# uc4h_airspeed_v0401.net
KiCad netlist of a schematic drawn in EAGLE
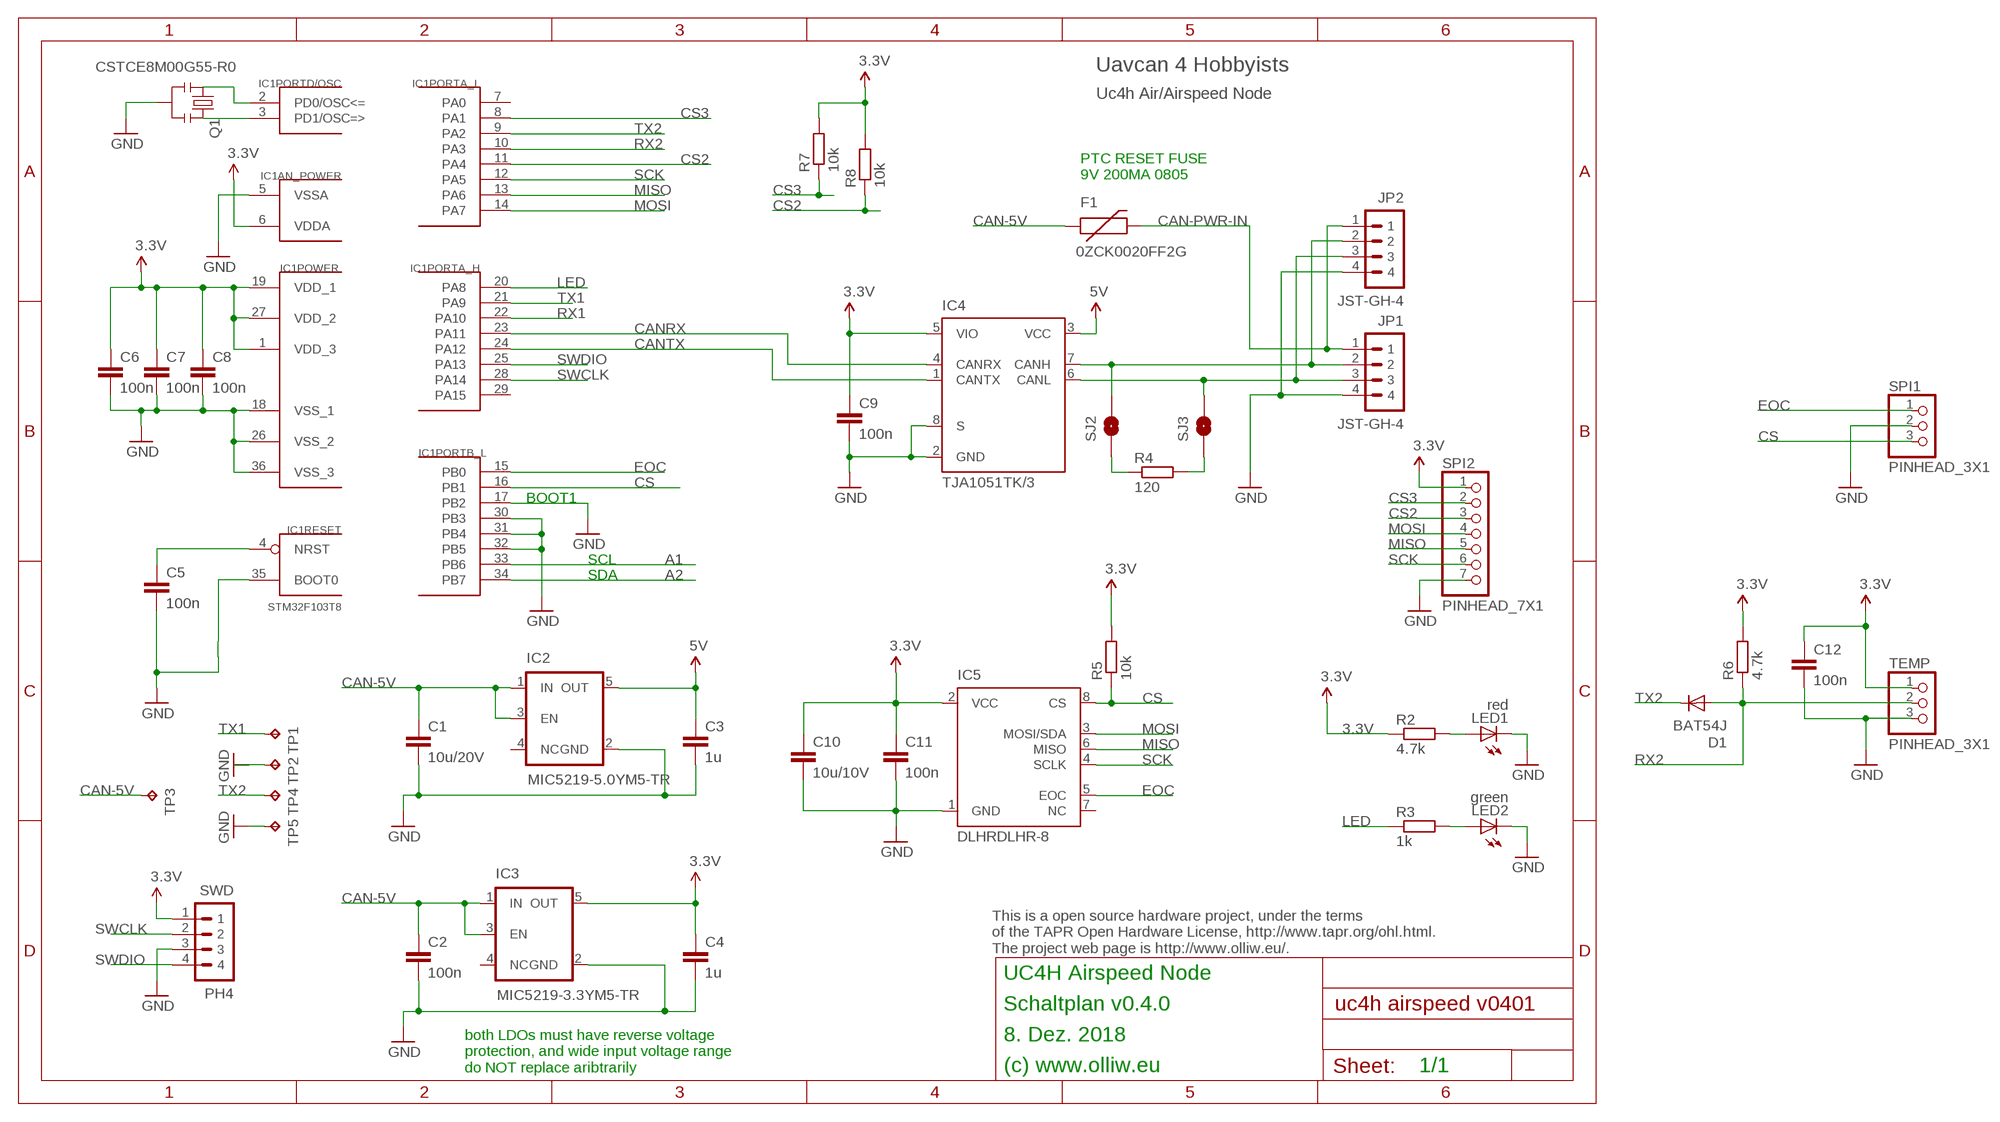
[diagram p0: schematic, sheet 1]

(export (version "E")
  (design (tool "Eeschema 10.0.6"))
  (components
    (comp (ref "C1")
      (value "10u/20V")
      (footprint "eagle-import:C1206")
      (libsource (lib "eagle-import") (part "C-EUC1206"))
    )
    (comp (ref "C2")
      (value "100n")
      (footprint "eagle-import:C0603K")
      (libsource (lib "eagle-import") (part "C-EUC0603K"))
    )
    (comp (ref "C3")
      (value "1u")
      (footprint "eagle-import:C0603K")
      (libsource (lib "eagle-import") (part "C-EUC0603K"))
    )
    (comp (ref "C4")
      (value "1u")
      (footprint "eagle-import:C0603K")
      (libsource (lib "eagle-import") (part "C-EUC0603K"))
    )
    (comp (ref "C5")
      (value "100n")
      (footprint "eagle-import:C0603K")
      (libsource (lib "eagle-import") (part "C-EUC0603K"))
    )
    (comp (ref "C6")
      (value "100n")
      (footprint "eagle-import:C0603K")
      (libsource (lib "eagle-import") (part "C-EUC0603K"))
    )
    (comp (ref "C7")
      (value "100n")
      (footprint "eagle-import:C0603K")
      (libsource (lib "eagle-import") (part "C-EUC0603K"))
    )
    (comp (ref "C8")
      (value "100n")
      (footprint "eagle-import:C0603K")
      (libsource (lib "eagle-import") (part "C-EUC0603K"))
    )
    (comp (ref "C9")
      (value "100n")
      (footprint "eagle-import:C0603K")
      (libsource (lib "eagle-import") (part "C-EUC0603K"))
    )
    (comp (ref "C10")
      (value "10u/10V")
      (footprint "eagle-import:C1206")
      (libsource (lib "eagle-import") (part "C-EUC1206"))
    )
    (comp (ref "C11")
      (value "100n")
      (footprint "eagle-import:C0603K")
      (libsource (lib "eagle-import") (part "C-EUC0603K"))
    )
    (comp (ref "C12")
      (value "100n")
      (footprint "eagle-import:C0603K")
      (libsource (lib "eagle-import") (part "C-EUC0603K"))
    )
    (comp (ref "D1")
      (value "BAT54J")
      (footprint "eagle-import:SOD110-R")
      (libsource (lib "eagle-import") (part "DIODE-SOD110-R"))
    )
    (comp (ref "F1")
      (value "0ZCK0020FF2G")
      (footprint "eagle-import:FUSE-0805")
      (libsource (lib "eagle-import") (part "FUSE-PTCFUSE-0805"))
    )
    (comp (ref "IC1")
      (value "STM32F103T8")
      (footprint "eagle-import:VFQFPN36")
      (libsource (lib "eagle-import") (part "STM32F10XTXU6"))
    )
    (comp (ref "IC2")
      (value "MIC5219-5.0YM5-TR")
      (footprint "eagle-import:SOT23-5")
      (libsource (lib "eagle-import") (part "V_REG_TPS76433SOT23-5"))
    )
    (comp (ref "IC3")
      (value "MIC5219-3.3YM5-TR")
      (footprint "eagle-import:SOT23-5")
      (libsource (lib "eagle-import") (part "V_REG_TPS76433SOT23-5"))
    )
    (comp (ref "IC4")
      (value "TJA1051TK/3")
      (footprint "eagle-import:HVSON8")
      (libsource (lib "eagle-import") (part "TJA1051TK/3"))
    )
    (comp (ref "IC5")
      (value "DLHRDLHR-8")
      (footprint "eagle-import:DLHR-8")
      (libsource (lib "eagle-import") (part "DLHRDLHR-8"))
    )
    (comp (ref "JP1")
      (value "JST-GH-4")
      (footprint "eagle-import:SM04B-GHS-TB")
      (libsource (lib "eagle-import") (part "JST-GH-4"))
    )
    (comp (ref "JP2")
      (value "JST-GH-4")
      (footprint "eagle-import:SM04B-GHS-TB")
      (libsource (lib "eagle-import") (part "JST-GH-4"))
    )
    (comp (ref "LED1")
      (value "red")
      (footprint "eagle-import:CHIPLED_0603")
      (libsource (lib "eagle-import") (part "LEDCHIPLED_0603"))
    )
    (comp (ref "LED2")
      (value "green")
      (footprint "eagle-import:CHIPLED_0603")
      (libsource (lib "eagle-import") (part "LEDCHIPLED_0603"))
    )
    (comp (ref "Q1")
      (value "CSTCE8M00G55-R0")
      (footprint "eagle-import:RESONATOR-SMD")
      (libsource (lib "eagle-import") (part "RESONATORSMD"))
    )
    (comp (ref "R2")
      (value "4.7k")
      (footprint "eagle-import:R0603")
      (libsource (lib "eagle-import") (part "R-EU_R0603"))
    )
    (comp (ref "R3")
      (value "1k")
      (footprint "eagle-import:R0603")
      (libsource (lib "eagle-import") (part "R-EU_R0603"))
    )
    (comp (ref "R4")
      (value "120")
      (footprint "eagle-import:R0603")
      (libsource (lib "eagle-import") (part "R-EU_R0603"))
    )
    (comp (ref "R5")
      (value "10k")
      (footprint "eagle-import:R0603")
      (libsource (lib "eagle-import") (part "R-EU_R0603"))
    )
    (comp (ref "R6")
      (value "4.7k")
      (footprint "eagle-import:R0603")
      (libsource (lib "eagle-import") (part "R-EU_R0603"))
    )
    (comp (ref "R7")
      (value "10k")
      (footprint "eagle-import:R0603")
      (libsource (lib "eagle-import") (part "R-EU_R0603"))
    )
    (comp (ref "R8")
      (value "10k")
      (footprint "eagle-import:R0603")
      (libsource (lib "eagle-import") (part "R-EU_R0603"))
    )
    (comp (ref "SJ2")
      (value "SOLDERJUMPERNO")
      (footprint "eagle-import:SJ_2S-NO")
      (libsource (lib "eagle-import") (part "SOLDERJUMPERNO"))
    )
    (comp (ref "SJ3")
      (value "SOLDERJUMPERNO")
      (footprint "eagle-import:SJ_2S-NO")
      (libsource (lib "eagle-import") (part "SOLDERJUMPERNO"))
    )
    (comp (ref "SPI1")
      (value "PINHEAD_3X1")
      (footprint "eagle-import:PINHEAD_3X1")
      (libsource (lib "eagle-import") (part "PINHEAD_3X1"))
    )
    (comp (ref "SPI2")
      (value "PINHEAD_7X1")
      (footprint "eagle-import:PINHEAD_7X1")
      (libsource (lib "eagle-import") (part "PINHEAD_7X1"))
    )
    (comp (ref "SWD")
      (value "PH4")
      (footprint "eagle-import:4X1_1P27_OCT_BILEX")
      (libsource (lib "eagle-import") (part "P4X1_1P27-OCT_BILEX"))
    )
    (comp (ref "TEMP")
      (value "PINHEAD_3X1")
      (footprint "eagle-import:PINHEAD_3X1")
      (libsource (lib "eagle-import") (part "PINHEAD_3X1"))
    )
    (comp (ref "TP1")
      (value "TPB1,27")
      (footprint "eagle-import:B1,27")
      (libsource (lib "eagle-import") (part "TPB1,27"))
    )
    (comp (ref "TP2")
      (value "TPB1,27")
      (footprint "eagle-import:B1,27")
      (libsource (lib "eagle-import") (part "TPB1,27"))
    )
    (comp (ref "TP3")
      (value "TPB1,27")
      (footprint "eagle-import:B1,27")
      (libsource (lib "eagle-import") (part "TPB1,27"))
    )
    (comp (ref "TP4")
      (value "TPB1,27")
      (footprint "eagle-import:B1,27")
      (libsource (lib "eagle-import") (part "TPB1,27"))
    )
    (comp (ref "TP5")
      (value "TPB1,27")
      (footprint "eagle-import:B1,27")
      (libsource (lib "eagle-import") (part "TPB1,27"))
    )
  )
  (nets
    (net (code "1") (name "/A1") (class "Default")
      (node (ref "IC1") (pin "33") (pinfunction "PB6_33") (pintype "bidirectional"))
    )
    (net (code "2") (name "/A2") (class "Default")
      (node (ref "IC1") (pin "34") (pinfunction "PB7_34") (pintype "bidirectional"))
    )
    (net (code "3") (name "/CAN-5V") (class "Default")
      (node (ref "C1") (pin "1") (pinfunction "1_1") (pintype "passive"))
      (node (ref "C2") (pin "1") (pinfunction "1_1") (pintype "passive"))
      (node (ref "F1") (pin "1") (pinfunction "1_1") (pintype "bidirectional"))
      (node (ref "IC2") (pin "1") (pinfunction "IN_1") (pintype "power_in"))
      (node (ref "IC2") (pin "3") (pinfunction "EN_3") (pintype "input"))
      (node (ref "IC3") (pin "1") (pinfunction "IN_1") (pintype "power_in"))
      (node (ref "IC3") (pin "3") (pinfunction "EN_3") (pintype "input"))
      (node (ref "TP3") (pin "TP") (pinfunction "TP_TP") (pintype "input"))
    )
    (net (code "4") (name "/CAN-PWR-IN") (class "Default")
      (node (ref "F1") (pin "2") (pinfunction "2_2") (pintype "bidirectional"))
      (node (ref "JP1") (pin "1") (pinfunction "1_1") (pintype "passive"))
      (node (ref "JP2") (pin "1") (pinfunction "1_1") (pintype "passive"))
    )
    (net (code "5") (name "/CANRX") (class "Default")
      (node (ref "IC1") (pin "23") (pinfunction "PA11_23") (pintype "bidirectional"))
      (node (ref "IC4") (pin "4") (pinfunction "CANRX_4") (pintype "output"))
    )
    (net (code "6") (name "/CANTX") (class "Default")
      (node (ref "IC1") (pin "24") (pinfunction "PA12_24") (pintype "bidirectional"))
      (node (ref "IC4") (pin "1") (pinfunction "CANTX_1") (pintype "input"))
    )
    (net (code "7") (name "/CS") (class "Default")
      (node (ref "IC1") (pin "16") (pinfunction "PB1_16") (pintype "bidirectional"))
      (node (ref "IC5") (pin "8") (pinfunction "CS_8") (pintype "input"))
      (node (ref "R5") (pin "1") (pinfunction "1_1") (pintype "passive"))
      (node (ref "SPI1") (pin "3") (pinfunction "5_3") (pintype "passive"))
    )
    (net (code "8") (name "/CS2") (class "Default")
      (node (ref "IC1") (pin "11") (pinfunction "PA4_11") (pintype "bidirectional"))
      (node (ref "R8") (pin "1") (pinfunction "1_1") (pintype "passive"))
      (node (ref "SPI2") (pin "3") (pinfunction "3_3") (pintype "passive"))
    )
    (net (code "9") (name "/CS3") (class "Default")
      (node (ref "IC1") (pin "8") (pinfunction "PA1_8") (pintype "bidirectional"))
      (node (ref "R7") (pin "1") (pinfunction "1_1") (pintype "passive"))
      (node (ref "SPI2") (pin "2") (pinfunction "2_2") (pintype "passive"))
    )
    (net (code "10") (name "/EOC") (class "Default")
      (node (ref "IC1") (pin "15") (pinfunction "PB0_15") (pintype "bidirectional"))
      (node (ref "IC5") (pin "5") (pinfunction "EOC_5") (pintype "output"))
      (node (ref "SPI1") (pin "1") (pinfunction "1_1") (pintype "passive"))
    )
    (net (code "11") (name "/LED") (class "Default")
      (node (ref "IC1") (pin "20") (pinfunction "PA8_20") (pintype "bidirectional"))
      (node (ref "R3") (pin "1") (pinfunction "1_1") (pintype "passive"))
    )
    (net (code "12") (name "/MISO") (class "Default")
      (node (ref "IC1") (pin "13") (pinfunction "PA6_13") (pintype "bidirectional"))
      (node (ref "IC5") (pin "6") (pinfunction "MISO_6") (pintype "output"))
      (node (ref "SPI2") (pin "5") (pinfunction "5_5") (pintype "passive"))
    )
    (net (code "13") (name "/MOSI") (class "Default")
      (node (ref "IC1") (pin "14") (pinfunction "PA7_14") (pintype "bidirectional"))
      (node (ref "IC5") (pin "3") (pinfunction "MOSI/SDA_3") (pintype "input"))
      (node (ref "SPI2") (pin "4") (pinfunction "4_4") (pintype "passive"))
    )
    (net (code "14") (name "/RX1") (class "Default")
      (node (ref "IC1") (pin "22") (pinfunction "PA10_22") (pintype "bidirectional"))
    )
    (net (code "15") (name "/RX2") (class "Default")
      (node (ref "D1") (pin "A") (pinfunction "A_A") (pintype "passive"))
      (node (ref "IC1") (pin "10") (pinfunction "PA3_10") (pintype "bidirectional"))
      (node (ref "R6") (pin "1") (pinfunction "1_1") (pintype "passive"))
      (node (ref "TEMP") (pin "2") (pinfunction "3_2") (pintype "passive"))
    )
    (net (code "16") (name "/SCK") (class "Default")
      (node (ref "IC1") (pin "12") (pinfunction "PA5_12") (pintype "bidirectional"))
      (node (ref "IC5") (pin "4") (pinfunction "SCLK_4") (pintype "input"))
      (node (ref "SPI2") (pin "6") (pinfunction "6_6") (pintype "passive"))
    )
    (net (code "17") (name "/SWCLK") (class "Default")
      (node (ref "IC1") (pin "28") (pinfunction "PA14_28") (pintype "bidirectional"))
      (node (ref "SWD") (pin "2") (pinfunction "2_2") (pintype "passive"))
    )
    (net (code "18") (name "/SWDIO") (class "Default")
      (node (ref "IC1") (pin "25") (pinfunction "PA13_25") (pintype "bidirectional"))
      (node (ref "SWD") (pin "4") (pinfunction "4_4") (pintype "passive"))
    )
    (net (code "19") (name "/TX1") (class "Default")
      (node (ref "IC1") (pin "21") (pinfunction "PA9_21") (pintype "bidirectional"))
      (node (ref "TP1") (pin "TP") (pinfunction "TP_TP") (pintype "input"))
    )
    (net (code "20") (name "/TX2") (class "Default")
      (node (ref "D1") (pin "C") (pinfunction "C_C") (pintype "passive"))
      (node (ref "IC1") (pin "9") (pinfunction "PA2_9") (pintype "bidirectional"))
      (node (ref "TP4") (pin "TP") (pinfunction "TP_TP") (pintype "input"))
    )
    (net (code "21") (name "3.3V") (class "Default")
      (node (ref "C10") (pin "1") (pinfunction "1_1") (pintype "passive"))
      (node (ref "C11") (pin "1") (pinfunction "1_1") (pintype "passive"))
      (node (ref "C12") (pin "1") (pinfunction "1_1") (pintype "passive"))
      (node (ref "C4") (pin "1") (pinfunction "1_1") (pintype "passive"))
      (node (ref "C6") (pin "1") (pinfunction "1_1") (pintype "passive"))
      (node (ref "C7") (pin "1") (pinfunction "1_1") (pintype "passive"))
      (node (ref "C8") (pin "1") (pinfunction "1_1") (pintype "passive"))
      (node (ref "C9") (pin "1") (pinfunction "1_1") (pintype "passive"))
      (node (ref "IC1") (pin "1") (pinfunction "VDD_3_1") (pintype "power_in"))
      (node (ref "IC1") (pin "19") (pinfunction "VDD_1_19") (pintype "power_in"))
      (node (ref "IC1") (pin "27") (pinfunction "VDD_2_27") (pintype "power_in"))
      (node (ref "IC1") (pin "6") (pinfunction "VDDA_6") (pintype "power_in"))
      (node (ref "IC3") (pin "5") (pinfunction "OUT_5") (pintype "output"))
      (node (ref "IC4") (pin "5") (pinfunction "VIO_5") (pintype "power_in"))
      (node (ref "IC5") (pin "2") (pinfunction "VCC_2") (pintype "power_in"))
      (node (ref "R2") (pin "1") (pinfunction "1_1") (pintype "passive"))
      (node (ref "R5") (pin "2") (pinfunction "2_2") (pintype "passive"))
      (node (ref "R6") (pin "2") (pinfunction "2_2") (pintype "passive"))
      (node (ref "R7") (pin "2") (pinfunction "2_2") (pintype "passive"))
      (node (ref "R8") (pin "2") (pinfunction "2_2") (pintype "passive"))
      (node (ref "SPI2") (pin "1") (pinfunction "1_1") (pintype "passive"))
      (node (ref "SWD") (pin "1") (pinfunction "1_1") (pintype "passive"))
      (node (ref "TEMP") (pin "1") (pinfunction "1_1") (pintype "passive"))
    )
    (net (code "22") (name "5V") (class "Default")
      (node (ref "C3") (pin "1") (pinfunction "1_1") (pintype "passive"))
      (node (ref "IC2") (pin "5") (pinfunction "OUT_5") (pintype "output"))
      (node (ref "IC4") (pin "3") (pinfunction "VCC_3") (pintype "power_in"))
    )
    (net (code "23") (name "GND") (class "Default")
      (node (ref "C1") (pin "2") (pinfunction "2_2") (pintype "passive"))
      (node (ref "C10") (pin "2") (pinfunction "2_2") (pintype "passive"))
      (node (ref "C11") (pin "2") (pinfunction "2_2") (pintype "passive"))
      (node (ref "C12") (pin "2") (pinfunction "2_2") (pintype "passive"))
      (node (ref "C2") (pin "2") (pinfunction "2_2") (pintype "passive"))
      (node (ref "C3") (pin "2") (pinfunction "2_2") (pintype "passive"))
      (node (ref "C4") (pin "2") (pinfunction "2_2") (pintype "passive"))
      (node (ref "C5") (pin "2") (pinfunction "2_2") (pintype "passive"))
      (node (ref "C6") (pin "2") (pinfunction "2_2") (pintype "passive"))
      (node (ref "C7") (pin "2") (pinfunction "2_2") (pintype "passive"))
      (node (ref "C8") (pin "2") (pinfunction "2_2") (pintype "passive"))
      (node (ref "C9") (pin "2") (pinfunction "2_2") (pintype "passive"))
      (node (ref "IC1") (pin "17") (pinfunction "PB2_17") (pintype "bidirectional"))
      (node (ref "IC1") (pin "18") (pinfunction "VSS_1_18") (pintype "power_in"))
      (node (ref "IC1") (pin "26") (pinfunction "VSS_2_26") (pintype "power_in"))
      (node (ref "IC1") (pin "30") (pinfunction "PB3_30") (pintype "bidirectional"))
      (node (ref "IC1") (pin "31") (pinfunction "PB4_31") (pintype "bidirectional"))
      (node (ref "IC1") (pin "32") (pinfunction "PB5_32") (pintype "bidirectional"))
      (node (ref "IC1") (pin "35") (pinfunction "BOOT0_35") (pintype "input"))
      (node (ref "IC1") (pin "36") (pinfunction "VSS_3_36") (pintype "power_in"))
      (node (ref "IC1") (pin "5") (pinfunction "VSSA_5") (pintype "power_in"))
      (node (ref "IC2") (pin "2") (pinfunction "GND_2") (pintype "power_in"))
      (node (ref "IC3") (pin "2") (pinfunction "GND_2") (pintype "power_in"))
      (node (ref "IC4") (pin "2") (pinfunction "GND_2") (pintype "power_in"))
      (node (ref "IC4") (pin "8") (pinfunction "S_8") (pintype "input"))
      (node (ref "IC5") (pin "1") (pinfunction "GND_1") (pintype "power_in"))
      (node (ref "JP1") (pin "4") (pinfunction "4_4") (pintype "passive"))
      (node (ref "JP2") (pin "4") (pinfunction "4_4") (pintype "passive"))
      (node (ref "LED1") (pin "C") (pinfunction "C_C") (pintype "passive"))
      (node (ref "LED2") (pin "C") (pinfunction "C_C") (pintype "passive"))
      (node (ref "Q1") (pin "2") (pinfunction "2_2") (pintype "passive"))
      (node (ref "SPI1") (pin "2") (pinfunction "3_2") (pintype "passive"))
      (node (ref "SPI2") (pin "7") (pinfunction "7_7") (pintype "passive"))
      (node (ref "SWD") (pin "3") (pinfunction "3_3") (pintype "passive"))
      (node (ref "TEMP") (pin "3") (pinfunction "5_3") (pintype "passive"))
      (node (ref "TP2") (pin "TP") (pinfunction "TP_TP") (pintype "input"))
      (node (ref "TP5") (pin "TP") (pinfunction "TP_TP") (pintype "input"))
    )
    (net (code "24") (name "Net-(IC1E-PD0{slash}OSC<=)") (class "Default")
      (node (ref "IC1") (pin "2") (pinfunction "PD0/OSC<=_2") (pintype "bidirectional"))
      (node (ref "Q1") (pin "1") (pinfunction "1_1") (pintype "passive"))
    )
    (net (code "25") (name "Net-(IC1E-PD1{slash}OSC=>)") (class "Default")
      (node (ref "IC1") (pin "3") (pinfunction "PD1/OSC=>_3") (pintype "bidirectional"))
      (node (ref "Q1") (pin "3") (pinfunction "3_3") (pintype "passive"))
    )
    (net (code "26") (name "Net-(IC1G-NRST)") (class "Default")
      (node (ref "C5") (pin "1") (pinfunction "1_1") (pintype "passive"))
      (node (ref "IC1") (pin "4") (pinfunction "NRST_4") (pintype "input"))
    )
    (net (code "27") (name "Net-(IC4-CANH)") (class "Default")
      (node (ref "IC4") (pin "7") (pinfunction "CANH_7") (pintype "bidirectional"))
      (node (ref "JP1") (pin "2") (pinfunction "2_2") (pintype "passive"))
      (node (ref "JP2") (pin "2") (pinfunction "2_2") (pintype "passive"))
      (node (ref "SJ2") (pin "2") (pinfunction "2_2") (pintype "passive"))
    )
    (net (code "28") (name "Net-(IC4-CANL)") (class "Default")
      (node (ref "IC4") (pin "6") (pinfunction "CANL_6") (pintype "bidirectional"))
      (node (ref "JP1") (pin "3") (pinfunction "3_3") (pintype "passive"))
      (node (ref "JP2") (pin "3") (pinfunction "3_3") (pintype "passive"))
      (node (ref "SJ3") (pin "2") (pinfunction "2_2") (pintype "passive"))
    )
    (net (code "29") (name "Net-(LED1-PadA)") (class "Default")
      (node (ref "LED1") (pin "A") (pinfunction "A_A") (pintype "passive"))
      (node (ref "R2") (pin "2") (pinfunction "2_2") (pintype "passive"))
    )
    (net (code "30") (name "Net-(LED2-PadA)") (class "Default")
      (node (ref "LED2") (pin "A") (pinfunction "A_A") (pintype "passive"))
      (node (ref "R3") (pin "2") (pinfunction "2_2") (pintype "passive"))
    )
    (net (code "31") (name "Net-(R4-Pad1)") (class "Default")
      (node (ref "R4") (pin "1") (pinfunction "1_1") (pintype "passive"))
      (node (ref "SJ2") (pin "1") (pinfunction "1_1") (pintype "passive"))
    )
    (net (code "32") (name "Net-(R4-Pad2)") (class "Default")
      (node (ref "R4") (pin "2") (pinfunction "2_2") (pintype "passive"))
      (node (ref "SJ3") (pin "1") (pinfunction "1_1") (pintype "passive"))
    )
    (net (code "33") (name "unconnected-(IC1B-PA15-Pad29)") (class "Default")
      (node (ref "IC1") (pin "29") (pinfunction "PA15_29") (pintype "bidirectional"))
    )
    (net (code "34") (name "unconnected-(IC1C-PA0-Pad7)") (class "Default")
      (node (ref "IC1") (pin "7") (pinfunction "PA0_7") (pintype "bidirectional"))
    )
    (net (code "35") (name "unconnected-(IC2-NC-Pad4)") (class "Default")
      (node (ref "IC2") (pin "4") (pinfunction "NC_4") (pintype "passive"))
    )
    (net (code "36") (name "unconnected-(IC3-NC-Pad4)") (class "Default")
      (node (ref "IC3") (pin "4") (pinfunction "NC_4") (pintype "passive"))
    )
    (net (code "37") (name "unconnected-(IC5-NC-Pad7)") (class "Default")
      (node (ref "IC5") (pin "7") (pinfunction "NC_7") (pintype "no_connect"))
    )
  )
)
